# OpenAGBoardPart2.net
KiCad netlist of a schematic drawn in Altium Designer
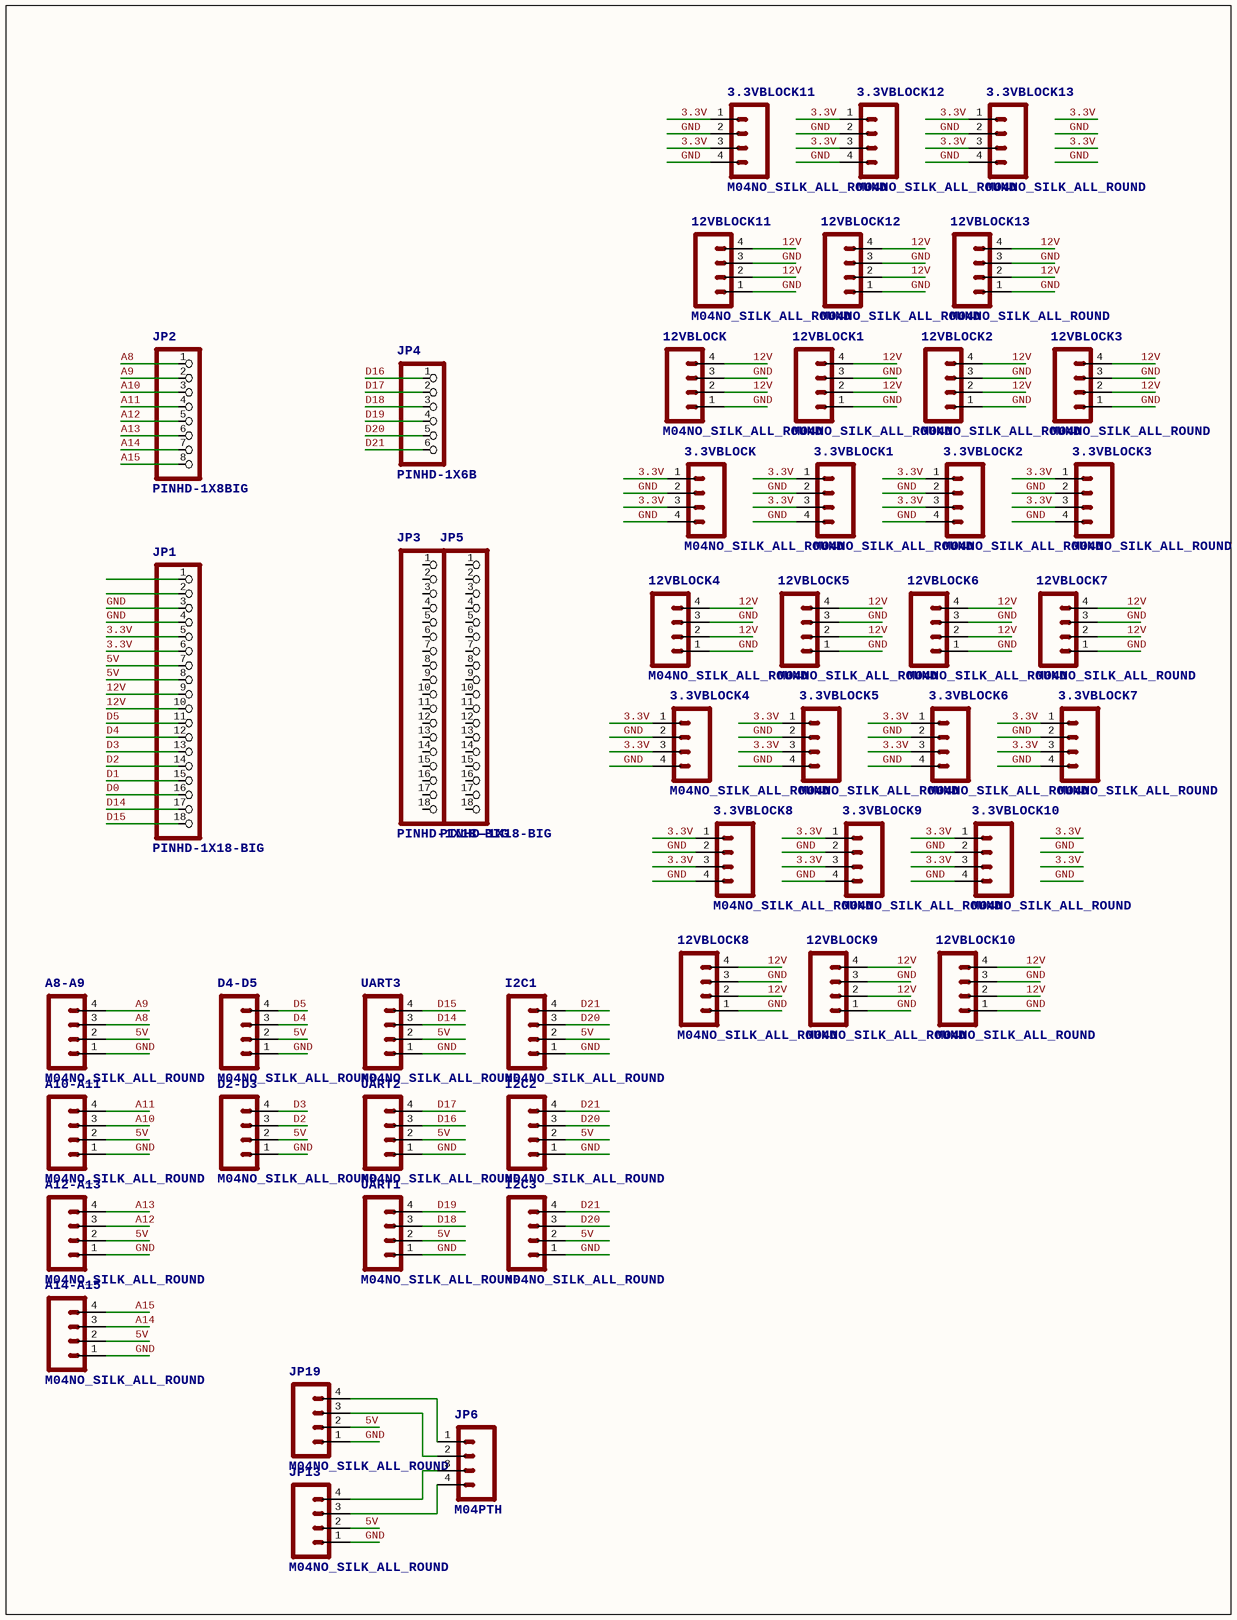
[diagram p0: OpenAGBoardPart2.SchDoc]

(export (version "E")
  (design (tool "Eeschema 10.0.6"))
  (components
    (comp (ref "3.3VBLOCK")
      (value "M04NO_SILK_ALL_ROUND")
      (footprint "1X04_NO_SILK_ALL_ROUND")
      (libsource (lib "SparkFun-Connectors") (part "M04NO_SILK_ALL_ROUND"))
    )
    (comp (ref "3.3VBLOCK1")
      (value "M04NO_SILK_ALL_ROUND")
      (footprint "1X04_NO_SILK_ALL_ROUND")
      (libsource (lib "SparkFun-Connectors") (part "M04NO_SILK_ALL_ROUND"))
    )
    (comp (ref "3.3VBLOCK2")
      (value "M04NO_SILK_ALL_ROUND")
      (footprint "1X04_NO_SILK_ALL_ROUND")
      (libsource (lib "SparkFun-Connectors") (part "M04NO_SILK_ALL_ROUND"))
    )
    (comp (ref "3.3VBLOCK3")
      (value "M04NO_SILK_ALL_ROUND")
      (footprint "1X04_NO_SILK_ALL_ROUND")
      (libsource (lib "SparkFun-Connectors") (part "M04NO_SILK_ALL_ROUND"))
    )
    (comp (ref "3.3VBLOCK4")
      (value "M04NO_SILK_ALL_ROUND")
      (footprint "1X04_NO_SILK_ALL_ROUND")
      (libsource (lib "SparkFun-Connectors") (part "M04NO_SILK_ALL_ROUND"))
    )
    (comp (ref "3.3VBLOCK5")
      (value "M04NO_SILK_ALL_ROUND")
      (footprint "1X04_NO_SILK_ALL_ROUND")
      (libsource (lib "SparkFun-Connectors") (part "M04NO_SILK_ALL_ROUND"))
    )
    (comp (ref "3.3VBLOCK6")
      (value "M04NO_SILK_ALL_ROUND")
      (footprint "1X04_NO_SILK_ALL_ROUND")
      (libsource (lib "SparkFun-Connectors") (part "M04NO_SILK_ALL_ROUND"))
    )
    (comp (ref "3.3VBLOCK7")
      (value "M04NO_SILK_ALL_ROUND")
      (footprint "1X04_NO_SILK_ALL_ROUND")
      (libsource (lib "SparkFun-Connectors") (part "M04NO_SILK_ALL_ROUND"))
    )
    (comp (ref "3.3VBLOCK8")
      (value "M04NO_SILK_ALL_ROUND")
      (footprint "1X04_NO_SILK_ALL_ROUND")
      (libsource (lib "SparkFun-Connectors") (part "M04NO_SILK_ALL_ROUND"))
    )
    (comp (ref "3.3VBLOCK9")
      (value "M04NO_SILK_ALL_ROUND")
      (footprint "1X04_NO_SILK_ALL_ROUND")
      (libsource (lib "SparkFun-Connectors") (part "M04NO_SILK_ALL_ROUND"))
    )
    (comp (ref "3.3VBLOCK10")
      (value "M04NO_SILK_ALL_ROUND")
      (footprint "1X04_NO_SILK_ALL_ROUND")
      (libsource (lib "SparkFun-Connectors") (part "M04NO_SILK_ALL_ROUND"))
    )
    (comp (ref "3.3VBLOCK11")
      (value "M04NO_SILK_ALL_ROUND")
      (footprint "1X04_NO_SILK_ALL_ROUND")
      (libsource (lib "SparkFun-Connectors") (part "M04NO_SILK_ALL_ROUND"))
    )
    (comp (ref "3.3VBLOCK12")
      (value "M04NO_SILK_ALL_ROUND")
      (footprint "1X04_NO_SILK_ALL_ROUND")
      (libsource (lib "SparkFun-Connectors") (part "M04NO_SILK_ALL_ROUND"))
    )
    (comp (ref "3.3VBLOCK13")
      (value "M04NO_SILK_ALL_ROUND")
      (footprint "1X04_NO_SILK_ALL_ROUND")
      (libsource (lib "SparkFun-Connectors") (part "M04NO_SILK_ALL_ROUND"))
    )
    (comp (ref "12VBLOCK")
      (value "M04NO_SILK_ALL_ROUND")
      (footprint "1X04_NO_SILK_ALL_ROUND")
      (libsource (lib "SparkFun-Connectors") (part "M04NO_SILK_ALL_ROUND"))
    )
    (comp (ref "12VBLOCK1")
      (value "M04NO_SILK_ALL_ROUND")
      (footprint "1X04_NO_SILK_ALL_ROUND")
      (libsource (lib "SparkFun-Connectors") (part "M04NO_SILK_ALL_ROUND"))
    )
    (comp (ref "12VBLOCK2")
      (value "M04NO_SILK_ALL_ROUND")
      (footprint "1X04_NO_SILK_ALL_ROUND")
      (libsource (lib "SparkFun-Connectors") (part "M04NO_SILK_ALL_ROUND"))
    )
    (comp (ref "12VBLOCK3")
      (value "M04NO_SILK_ALL_ROUND")
      (footprint "1X04_NO_SILK_ALL_ROUND")
      (libsource (lib "SparkFun-Connectors") (part "M04NO_SILK_ALL_ROUND"))
    )
    (comp (ref "12VBLOCK4")
      (value "M04NO_SILK_ALL_ROUND")
      (footprint "1X04_NO_SILK_ALL_ROUND")
      (libsource (lib "SparkFun-Connectors") (part "M04NO_SILK_ALL_ROUND"))
    )
    (comp (ref "12VBLOCK5")
      (value "M04NO_SILK_ALL_ROUND")
      (footprint "1X04_NO_SILK_ALL_ROUND")
      (libsource (lib "SparkFun-Connectors") (part "M04NO_SILK_ALL_ROUND"))
    )
    (comp (ref "12VBLOCK6")
      (value "M04NO_SILK_ALL_ROUND")
      (footprint "1X04_NO_SILK_ALL_ROUND")
      (libsource (lib "SparkFun-Connectors") (part "M04NO_SILK_ALL_ROUND"))
    )
    (comp (ref "12VBLOCK7")
      (value "M04NO_SILK_ALL_ROUND")
      (footprint "1X04_NO_SILK_ALL_ROUND")
      (libsource (lib "SparkFun-Connectors") (part "M04NO_SILK_ALL_ROUND"))
    )
    (comp (ref "12VBLOCK8")
      (value "M04NO_SILK_ALL_ROUND")
      (footprint "1X04_NO_SILK_ALL_ROUND")
      (libsource (lib "SparkFun-Connectors") (part "M04NO_SILK_ALL_ROUND"))
    )
    (comp (ref "12VBLOCK9")
      (value "M04NO_SILK_ALL_ROUND")
      (footprint "1X04_NO_SILK_ALL_ROUND")
      (libsource (lib "SparkFun-Connectors") (part "M04NO_SILK_ALL_ROUND"))
    )
    (comp (ref "12VBLOCK10")
      (value "M04NO_SILK_ALL_ROUND")
      (footprint "1X04_NO_SILK_ALL_ROUND")
      (libsource (lib "SparkFun-Connectors") (part "M04NO_SILK_ALL_ROUND"))
    )
    (comp (ref "12VBLOCK11")
      (value "M04NO_SILK_ALL_ROUND")
      (footprint "1X04_NO_SILK_ALL_ROUND")
      (libsource (lib "SparkFun-Connectors") (part "M04NO_SILK_ALL_ROUND"))
    )
    (comp (ref "12VBLOCK12")
      (value "M04NO_SILK_ALL_ROUND")
      (footprint "1X04_NO_SILK_ALL_ROUND")
      (libsource (lib "SparkFun-Connectors") (part "M04NO_SILK_ALL_ROUND"))
    )
    (comp (ref "12VBLOCK13")
      (value "M04NO_SILK_ALL_ROUND")
      (footprint "1X04_NO_SILK_ALL_ROUND")
      (libsource (lib "SparkFun-Connectors") (part "M04NO_SILK_ALL_ROUND"))
    )
    (comp (ref "A8-A9")
      (value "M04NO_SILK_ALL_ROUND")
      (footprint "1X04_NO_SILK_ALL_ROUND")
      (libsource (lib "SparkFun-Connectors") (part "M04NO_SILK_ALL_ROUND"))
    )
    (comp (ref "A10-A11")
      (value "M04NO_SILK_ALL_ROUND")
      (footprint "1X04_NO_SILK_ALL_ROUND")
      (libsource (lib "SparkFun-Connectors") (part "M04NO_SILK_ALL_ROUND"))
    )
    (comp (ref "A12-A13")
      (value "M04NO_SILK_ALL_ROUND")
      (footprint "1X04_NO_SILK_ALL_ROUND")
      (libsource (lib "SparkFun-Connectors") (part "M04NO_SILK_ALL_ROUND"))
    )
    (comp (ref "A14-A15")
      (value "M04NO_SILK_ALL_ROUND")
      (footprint "1X04_NO_SILK_ALL_ROUND")
      (libsource (lib "SparkFun-Connectors") (part "M04NO_SILK_ALL_ROUND"))
    )
    (comp (ref "D2-D3")
      (value "M04NO_SILK_ALL_ROUND")
      (footprint "1X04_NO_SILK_ALL_ROUND")
      (libsource (lib "SparkFun-Connectors") (part "M04NO_SILK_ALL_ROUND"))
    )
    (comp (ref "D4-D5")
      (value "M04NO_SILK_ALL_ROUND")
      (footprint "1X04_NO_SILK_ALL_ROUND")
      (libsource (lib "SparkFun-Connectors") (part "M04NO_SILK_ALL_ROUND"))
    )
    (comp (ref "I2C1")
      (value "M04NO_SILK_ALL_ROUND")
      (footprint "1X04_NO_SILK_ALL_ROUND")
      (libsource (lib "SparkFun-Connectors") (part "M04NO_SILK_ALL_ROUND"))
    )
    (comp (ref "I2C2")
      (value "M04NO_SILK_ALL_ROUND")
      (footprint "1X04_NO_SILK_ALL_ROUND")
      (libsource (lib "SparkFun-Connectors") (part "M04NO_SILK_ALL_ROUND"))
    )
    (comp (ref "I2C3")
      (value "M04NO_SILK_ALL_ROUND")
      (footprint "1X04_NO_SILK_ALL_ROUND")
      (libsource (lib "SparkFun-Connectors") (part "M04NO_SILK_ALL_ROUND"))
    )
    (comp (ref "JP1")
      (value "PINHD-1X18-BIG")
      (footprint "1X18-BIG")
      (description "PIN HEADER")
      (libsource (lib "adafruit") (part "PINHD-1X18-BIG"))
    )
    (comp (ref "JP2")
      (value "PINHD-1X8BIG")
      (footprint "1X08-BIG")
      (description "PIN HEADER")
      (libsource (lib "adafruit") (part "PINHD-1X8BIG"))
    )
    (comp (ref "JP3")
      (value "PINHD-1X18-BIG")
      (footprint "1X18-BIG")
      (description "PIN HEADER")
      (libsource (lib "adafruit") (part "PINHD-1X18-BIG"))
    )
    (comp (ref "JP4")
      (value "PINHD-1X6B")
      (footprint "1X06-BIG")
      (description "PIN HEADER")
      (libsource (lib "adafruit") (part "PINHD-1X6B"))
    )
    (comp (ref "JP5")
      (value "PINHD-1X18-BIG")
      (footprint "1X18-BIG")
      (description "PIN HEADER")
      (libsource (lib "adafruit") (part "PINHD-1X18-BIG"))
    )
    (comp (ref "JP6")
      (value "M04PTH")
      (footprint "1X04")
      (libsource (lib "SparkFun-Connectors") (part "M04PTH"))
    )
    (comp (ref "JP13")
      (value "M04NO_SILK_ALL_ROUND")
      (footprint "1X04_NO_SILK_ALL_ROUND")
      (libsource (lib "SparkFun-Connectors") (part "M04NO_SILK_ALL_ROUND"))
    )
    (comp (ref "JP19")
      (value "M04NO_SILK_ALL_ROUND")
      (footprint "1X04_NO_SILK_ALL_ROUND")
      (libsource (lib "SparkFun-Connectors") (part "M04NO_SILK_ALL_ROUND"))
    )
    (comp (ref "UART1")
      (value "M04NO_SILK_ALL_ROUND")
      (footprint "1X04_NO_SILK_ALL_ROUND")
      (libsource (lib "SparkFun-Connectors") (part "M04NO_SILK_ALL_ROUND"))
    )
    (comp (ref "UART2")
      (value "M04NO_SILK_ALL_ROUND")
      (footprint "1X04_NO_SILK_ALL_ROUND")
      (libsource (lib "SparkFun-Connectors") (part "M04NO_SILK_ALL_ROUND"))
    )
    (comp (ref "UART3")
      (value "M04NO_SILK_ALL_ROUND")
      (footprint "1X04_NO_SILK_ALL_ROUND")
      (libsource (lib "SparkFun-Connectors") (part "M04NO_SILK_ALL_ROUND"))
    )
  )
  (nets
    (net (code "1") (name "/3.3V") (class "Default")
      (node (ref "3.3VBLOCK") (pin "1") (pinfunction "1_1") (pintype "passive"))
      (node (ref "3.3VBLOCK") (pin "3") (pinfunction "3_3") (pintype "passive"))
      (node (ref "3.3VBLOCK1") (pin "1") (pinfunction "1_1") (pintype "passive"))
      (node (ref "3.3VBLOCK1") (pin "3") (pinfunction "3_3") (pintype "passive"))
      (node (ref "3.3VBLOCK10") (pin "1") (pinfunction "1_1") (pintype "passive"))
      (node (ref "3.3VBLOCK10") (pin "3") (pinfunction "3_3") (pintype "passive"))
      (node (ref "3.3VBLOCK11") (pin "1") (pinfunction "1_1") (pintype "passive"))
      (node (ref "3.3VBLOCK11") (pin "3") (pinfunction "3_3") (pintype "passive"))
      (node (ref "3.3VBLOCK12") (pin "1") (pinfunction "1_1") (pintype "passive"))
      (node (ref "3.3VBLOCK12") (pin "3") (pinfunction "3_3") (pintype "passive"))
      (node (ref "3.3VBLOCK13") (pin "1") (pinfunction "1_1") (pintype "passive"))
      (node (ref "3.3VBLOCK13") (pin "3") (pinfunction "3_3") (pintype "passive"))
      (node (ref "3.3VBLOCK2") (pin "1") (pinfunction "1_1") (pintype "passive"))
      (node (ref "3.3VBLOCK2") (pin "3") (pinfunction "3_3") (pintype "passive"))
      (node (ref "3.3VBLOCK3") (pin "1") (pinfunction "1_1") (pintype "passive"))
      (node (ref "3.3VBLOCK3") (pin "3") (pinfunction "3_3") (pintype "passive"))
      (node (ref "3.3VBLOCK4") (pin "1") (pinfunction "1_1") (pintype "passive"))
      (node (ref "3.3VBLOCK4") (pin "3") (pinfunction "3_3") (pintype "passive"))
      (node (ref "3.3VBLOCK5") (pin "1") (pinfunction "1_1") (pintype "passive"))
      (node (ref "3.3VBLOCK5") (pin "3") (pinfunction "3_3") (pintype "passive"))
      (node (ref "3.3VBLOCK6") (pin "1") (pinfunction "1_1") (pintype "passive"))
      (node (ref "3.3VBLOCK6") (pin "3") (pinfunction "3_3") (pintype "passive"))
      (node (ref "3.3VBLOCK7") (pin "1") (pinfunction "1_1") (pintype "passive"))
      (node (ref "3.3VBLOCK7") (pin "3") (pinfunction "3_3") (pintype "passive"))
      (node (ref "3.3VBLOCK8") (pin "1") (pinfunction "1_1") (pintype "passive"))
      (node (ref "3.3VBLOCK8") (pin "3") (pinfunction "3_3") (pintype "passive"))
      (node (ref "3.3VBLOCK9") (pin "1") (pinfunction "1_1") (pintype "passive"))
      (node (ref "3.3VBLOCK9") (pin "3") (pinfunction "3_3") (pintype "passive"))
      (node (ref "JP1") (pin "5") (pinfunction "5_5") (pintype "passive"))
      (node (ref "JP1") (pin "6") (pinfunction "6_6") (pintype "passive"))
    )
    (net (code "2") (name "/5V") (class "Default")
      (node (ref "A10-A11") (pin "2") (pinfunction "2_2") (pintype "passive"))
      (node (ref "A12-A13") (pin "2") (pinfunction "2_2") (pintype "passive"))
      (node (ref "A14-A15") (pin "2") (pinfunction "2_2") (pintype "passive"))
      (node (ref "A8-A9") (pin "2") (pinfunction "2_2") (pintype "passive"))
      (node (ref "D2-D3") (pin "2") (pinfunction "2_2") (pintype "passive"))
      (node (ref "D4-D5") (pin "2") (pinfunction "2_2") (pintype "passive"))
      (node (ref "I2C1") (pin "2") (pinfunction "2_2") (pintype "passive"))
      (node (ref "I2C2") (pin "2") (pinfunction "2_2") (pintype "passive"))
      (node (ref "I2C3") (pin "2") (pinfunction "2_2") (pintype "passive"))
      (node (ref "JP1") (pin "7") (pinfunction "7_7") (pintype "passive"))
      (node (ref "JP1") (pin "8") (pinfunction "8_8") (pintype "passive"))
      (node (ref "JP13") (pin "2") (pinfunction "2_2") (pintype "passive"))
      (node (ref "JP19") (pin "2") (pinfunction "2_2") (pintype "passive"))
      (node (ref "UART1") (pin "2") (pinfunction "2_2") (pintype "passive"))
      (node (ref "UART2") (pin "2") (pinfunction "2_2") (pintype "passive"))
      (node (ref "UART3") (pin "2") (pinfunction "2_2") (pintype "passive"))
    )
    (net (code "3") (name "/12V") (class "Default")
      (node (ref "12VBLOCK") (pin "2") (pinfunction "2_2") (pintype "passive"))
      (node (ref "12VBLOCK") (pin "4") (pinfunction "4_4") (pintype "passive"))
      (node (ref "12VBLOCK1") (pin "2") (pinfunction "2_2") (pintype "passive"))
      (node (ref "12VBLOCK1") (pin "4") (pinfunction "4_4") (pintype "passive"))
      (node (ref "12VBLOCK10") (pin "2") (pinfunction "2_2") (pintype "passive"))
      (node (ref "12VBLOCK10") (pin "4") (pinfunction "4_4") (pintype "passive"))
      (node (ref "12VBLOCK11") (pin "2") (pinfunction "2_2") (pintype "passive"))
      (node (ref "12VBLOCK11") (pin "4") (pinfunction "4_4") (pintype "passive"))
      (node (ref "12VBLOCK12") (pin "2") (pinfunction "2_2") (pintype "passive"))
      (node (ref "12VBLOCK12") (pin "4") (pinfunction "4_4") (pintype "passive"))
      (node (ref "12VBLOCK13") (pin "2") (pinfunction "2_2") (pintype "passive"))
      (node (ref "12VBLOCK13") (pin "4") (pinfunction "4_4") (pintype "passive"))
      (node (ref "12VBLOCK2") (pin "2") (pinfunction "2_2") (pintype "passive"))
      (node (ref "12VBLOCK2") (pin "4") (pinfunction "4_4") (pintype "passive"))
      (node (ref "12VBLOCK3") (pin "2") (pinfunction "2_2") (pintype "passive"))
      (node (ref "12VBLOCK3") (pin "4") (pinfunction "4_4") (pintype "passive"))
      (node (ref "12VBLOCK4") (pin "2") (pinfunction "2_2") (pintype "passive"))
      (node (ref "12VBLOCK4") (pin "4") (pinfunction "4_4") (pintype "passive"))
      (node (ref "12VBLOCK5") (pin "2") (pinfunction "2_2") (pintype "passive"))
      (node (ref "12VBLOCK5") (pin "4") (pinfunction "4_4") (pintype "passive"))
      (node (ref "12VBLOCK6") (pin "2") (pinfunction "2_2") (pintype "passive"))
      (node (ref "12VBLOCK6") (pin "4") (pinfunction "4_4") (pintype "passive"))
      (node (ref "12VBLOCK7") (pin "2") (pinfunction "2_2") (pintype "passive"))
      (node (ref "12VBLOCK7") (pin "4") (pinfunction "4_4") (pintype "passive"))
      (node (ref "12VBLOCK8") (pin "2") (pinfunction "2_2") (pintype "passive"))
      (node (ref "12VBLOCK8") (pin "4") (pinfunction "4_4") (pintype "passive"))
      (node (ref "12VBLOCK9") (pin "2") (pinfunction "2_2") (pintype "passive"))
      (node (ref "12VBLOCK9") (pin "4") (pinfunction "4_4") (pintype "passive"))
      (node (ref "JP1") (pin "10") (pinfunction "10_10") (pintype "passive"))
      (node (ref "JP1") (pin "9") (pinfunction "9_9") (pintype "passive"))
    )
    (net (code "4") (name "/A8") (class "Default")
      (node (ref "A8-A9") (pin "3") (pinfunction "3_3") (pintype "passive"))
      (node (ref "JP2") (pin "1") (pinfunction "1_1") (pintype "passive"))
    )
    (net (code "5") (name "/A9") (class "Default")
      (node (ref "A8-A9") (pin "4") (pinfunction "4_4") (pintype "passive"))
      (node (ref "JP2") (pin "2") (pinfunction "2_2") (pintype "passive"))
    )
    (net (code "6") (name "/A10") (class "Default")
      (node (ref "A10-A11") (pin "3") (pinfunction "3_3") (pintype "passive"))
      (node (ref "JP2") (pin "3") (pinfunction "3_3") (pintype "passive"))
    )
    (net (code "7") (name "/A11") (class "Default")
      (node (ref "A10-A11") (pin "4") (pinfunction "4_4") (pintype "passive"))
      (node (ref "JP2") (pin "4") (pinfunction "4_4") (pintype "passive"))
    )
    (net (code "8") (name "/A12") (class "Default")
      (node (ref "A12-A13") (pin "3") (pinfunction "3_3") (pintype "passive"))
      (node (ref "JP2") (pin "5") (pinfunction "5_5") (pintype "passive"))
    )
    (net (code "9") (name "/A13") (class "Default")
      (node (ref "A12-A13") (pin "4") (pinfunction "4_4") (pintype "passive"))
      (node (ref "JP2") (pin "6") (pinfunction "6_6") (pintype "passive"))
    )
    (net (code "10") (name "/A14") (class "Default")
      (node (ref "A14-A15") (pin "3") (pinfunction "3_3") (pintype "passive"))
      (node (ref "JP2") (pin "7") (pinfunction "7_7") (pintype "passive"))
    )
    (net (code "11") (name "/A15") (class "Default")
      (node (ref "A14-A15") (pin "4") (pinfunction "4_4") (pintype "passive"))
      (node (ref "JP2") (pin "8") (pinfunction "8_8") (pintype "passive"))
    )
    (net (code "12") (name "/D0") (class "Default")
      (node (ref "JP1") (pin "16") (pinfunction "16_16") (pintype "passive"))
    )
    (net (code "13") (name "/D1") (class "Default")
      (node (ref "JP1") (pin "15") (pinfunction "15_15") (pintype "passive"))
    )
    (net (code "14") (name "/D2") (class "Default")
      (node (ref "D2-D3") (pin "3") (pinfunction "3_3") (pintype "passive"))
      (node (ref "JP1") (pin "14") (pinfunction "14_14") (pintype "passive"))
    )
    (net (code "15") (name "/D3") (class "Default")
      (node (ref "D2-D3") (pin "4") (pinfunction "4_4") (pintype "passive"))
      (node (ref "JP1") (pin "13") (pinfunction "13_13") (pintype "passive"))
    )
    (net (code "16") (name "/D4") (class "Default")
      (node (ref "D4-D5") (pin "3") (pinfunction "3_3") (pintype "passive"))
      (node (ref "JP1") (pin "12") (pinfunction "12_12") (pintype "passive"))
    )
    (net (code "17") (name "/D5") (class "Default")
      (node (ref "D4-D5") (pin "4") (pinfunction "4_4") (pintype "passive"))
      (node (ref "JP1") (pin "11") (pinfunction "11_11") (pintype "passive"))
    )
    (net (code "18") (name "/D14") (class "Default")
      (node (ref "JP1") (pin "17") (pinfunction "17_17") (pintype "passive"))
      (node (ref "UART3") (pin "3") (pinfunction "3_3") (pintype "passive"))
    )
    (net (code "19") (name "/D15") (class "Default")
      (node (ref "JP1") (pin "18") (pinfunction "18_18") (pintype "passive"))
      (node (ref "UART3") (pin "4") (pinfunction "4_4") (pintype "passive"))
    )
    (net (code "20") (name "/D16") (class "Default")
      (node (ref "JP4") (pin "1") (pinfunction "1_1") (pintype "passive"))
      (node (ref "UART2") (pin "3") (pinfunction "3_3") (pintype "passive"))
    )
    (net (code "21") (name "/D17") (class "Default")
      (node (ref "JP4") (pin "2") (pinfunction "2_2") (pintype "passive"))
      (node (ref "UART2") (pin "4") (pinfunction "4_4") (pintype "passive"))
    )
    (net (code "22") (name "/D18") (class "Default")
      (node (ref "JP4") (pin "3") (pinfunction "3_3") (pintype "passive"))
      (node (ref "UART1") (pin "3") (pinfunction "3_3") (pintype "passive"))
    )
    (net (code "23") (name "/D19") (class "Default")
      (node (ref "JP4") (pin "4") (pinfunction "4_4") (pintype "passive"))
      (node (ref "UART1") (pin "4") (pinfunction "4_4") (pintype "passive"))
    )
    (net (code "24") (name "/D20") (class "Default")
      (node (ref "I2C1") (pin "3") (pinfunction "3_3") (pintype "passive"))
      (node (ref "I2C2") (pin "3") (pinfunction "3_3") (pintype "passive"))
      (node (ref "I2C3") (pin "3") (pinfunction "3_3") (pintype "passive"))
      (node (ref "JP4") (pin "5") (pinfunction "5_5") (pintype "passive"))
    )
    (net (code "25") (name "/D21") (class "Default")
      (node (ref "I2C1") (pin "4") (pinfunction "4_4") (pintype "passive"))
      (node (ref "I2C2") (pin "4") (pinfunction "4_4") (pintype "passive"))
      (node (ref "I2C3") (pin "4") (pinfunction "4_4") (pintype "passive"))
      (node (ref "JP4") (pin "6") (pinfunction "6_6") (pintype "passive"))
    )
    (net (code "26") (name "/GND") (class "Default")
      (node (ref "12VBLOCK") (pin "1") (pinfunction "1_1") (pintype "passive"))
      (node (ref "12VBLOCK") (pin "3") (pinfunction "3_3") (pintype "passive"))
      (node (ref "12VBLOCK1") (pin "1") (pinfunction "1_1") (pintype "passive"))
      (node (ref "12VBLOCK1") (pin "3") (pinfunction "3_3") (pintype "passive"))
      (node (ref "12VBLOCK10") (pin "1") (pinfunction "1_1") (pintype "passive"))
      (node (ref "12VBLOCK10") (pin "3") (pinfunction "3_3") (pintype "passive"))
      (node (ref "12VBLOCK11") (pin "1") (pinfunction "1_1") (pintype "passive"))
      (node (ref "12VBLOCK11") (pin "3") (pinfunction "3_3") (pintype "passive"))
      (node (ref "12VBLOCK12") (pin "1") (pinfunction "1_1") (pintype "passive"))
      (node (ref "12VBLOCK12") (pin "3") (pinfunction "3_3") (pintype "passive"))
      (node (ref "12VBLOCK13") (pin "1") (pinfunction "1_1") (pintype "passive"))
      (node (ref "12VBLOCK13") (pin "3") (pinfunction "3_3") (pintype "passive"))
      (node (ref "12VBLOCK2") (pin "1") (pinfunction "1_1") (pintype "passive"))
      (node (ref "12VBLOCK2") (pin "3") (pinfunction "3_3") (pintype "passive"))
      (node (ref "12VBLOCK3") (pin "1") (pinfunction "1_1") (pintype "passive"))
      (node (ref "12VBLOCK3") (pin "3") (pinfunction "3_3") (pintype "passive"))
      (node (ref "12VBLOCK4") (pin "1") (pinfunction "1_1") (pintype "passive"))
      (node (ref "12VBLOCK4") (pin "3") (pinfunction "3_3") (pintype "passive"))
      (node (ref "12VBLOCK5") (pin "1") (pinfunction "1_1") (pintype "passive"))
      (node (ref "12VBLOCK5") (pin "3") (pinfunction "3_3") (pintype "passive"))
      (node (ref "12VBLOCK6") (pin "1") (pinfunction "1_1") (pintype "passive"))
      (node (ref "12VBLOCK6") (pin "3") (pinfunction "3_3") (pintype "passive"))
      (node (ref "12VBLOCK7") (pin "1") (pinfunction "1_1") (pintype "passive"))
      (node (ref "12VBLOCK7") (pin "3") (pinfunction "3_3") (pintype "passive"))
      (node (ref "12VBLOCK8") (pin "1") (pinfunction "1_1") (pintype "passive"))
      (node (ref "12VBLOCK8") (pin "3") (pinfunction "3_3") (pintype "passive"))
      (node (ref "12VBLOCK9") (pin "1") (pinfunction "1_1") (pintype "passive"))
      (node (ref "12VBLOCK9") (pin "3") (pinfunction "3_3") (pintype "passive"))
      (node (ref "3.3VBLOCK") (pin "2") (pinfunction "2_2") (pintype "passive"))
      (node (ref "3.3VBLOCK") (pin "4") (pinfunction "4_4") (pintype "passive"))
      (node (ref "3.3VBLOCK1") (pin "2") (pinfunction "2_2") (pintype "passive"))
      (node (ref "3.3VBLOCK1") (pin "4") (pinfunction "4_4") (pintype "passive"))
      (node (ref "3.3VBLOCK10") (pin "2") (pinfunction "2_2") (pintype "passive"))
      (node (ref "3.3VBLOCK10") (pin "4") (pinfunction "4_4") (pintype "passive"))
      (node (ref "3.3VBLOCK11") (pin "2") (pinfunction "2_2") (pintype "passive"))
      (node (ref "3.3VBLOCK11") (pin "4") (pinfunction "4_4") (pintype "passive"))
      (node (ref "3.3VBLOCK12") (pin "2") (pinfunction "2_2") (pintype "passive"))
      (node (ref "3.3VBLOCK12") (pin "4") (pinfunction "4_4") (pintype "passive"))
      (node (ref "3.3VBLOCK13") (pin "2") (pinfunction "2_2") (pintype "passive"))
      (node (ref "3.3VBLOCK13") (pin "4") (pinfunction "4_4") (pintype "passive"))
      (node (ref "3.3VBLOCK2") (pin "2") (pinfunction "2_2") (pintype "passive"))
      (node (ref "3.3VBLOCK2") (pin "4") (pinfunction "4_4") (pintype "passive"))
      (node (ref "3.3VBLOCK3") (pin "2") (pinfunction "2_2") (pintype "passive"))
      (node (ref "3.3VBLOCK3") (pin "4") (pinfunction "4_4") (pintype "passive"))
      (node (ref "3.3VBLOCK4") (pin "2") (pinfunction "2_2") (pintype "passive"))
      (node (ref "3.3VBLOCK4") (pin "4") (pinfunction "4_4") (pintype "passive"))
      (node (ref "3.3VBLOCK5") (pin "2") (pinfunction "2_2") (pintype "passive"))
      (node (ref "3.3VBLOCK5") (pin "4") (pinfunction "4_4") (pintype "passive"))
      (node (ref "3.3VBLOCK6") (pin "2") (pinfunction "2_2") (pintype "passive"))
      (node (ref "3.3VBLOCK6") (pin "4") (pinfunction "4_4") (pintype "passive"))
      (node (ref "3.3VBLOCK7") (pin "2") (pinfunction "2_2") (pintype "passive"))
      (node (ref "3.3VBLOCK7") (pin "4") (pinfunction "4_4") (pintype "passive"))
      (node (ref "3.3VBLOCK8") (pin "2") (pinfunction "2_2") (pintype "passive"))
      (node (ref "3.3VBLOCK8") (pin "4") (pinfunction "4_4") (pintype "passive"))
      (node (ref "3.3VBLOCK9") (pin "2") (pinfunction "2_2") (pintype "passive"))
      (node (ref "3.3VBLOCK9") (pin "4") (pinfunction "4_4") (pintype "passive"))
      (node (ref "A10-A11") (pin "1") (pinfunction "1_1") (pintype "passive"))
      (node (ref "A12-A13") (pin "1") (pinfunction "1_1") (pintype "passive"))
      (node (ref "A14-A15") (pin "1") (pinfunction "1_1") (pintype "passive"))
      (node (ref "A8-A9") (pin "1") (pinfunction "1_1") (pintype "passive"))
      (node (ref "D2-D3") (pin "1") (pinfunction "1_1") (pintype "passive"))
      (node (ref "D4-D5") (pin "1") (pinfunction "1_1") (pintype "passive"))
      (node (ref "I2C1") (pin "1") (pinfunction "1_1") (pintype "passive"))
      (node (ref "I2C2") (pin "1") (pinfunction "1_1") (pintype "passive"))
      (node (ref "I2C3") (pin "1") (pinfunction "1_1") (pintype "passive"))
      (node (ref "JP1") (pin "3") (pinfunction "3_3") (pintype "passive"))
      (node (ref "JP1") (pin "4") (pinfunction "4_4") (pintype "passive"))
      (node (ref "JP13") (pin "1") (pinfunction "1_1") (pintype "passive"))
      (node (ref "JP19") (pin "1") (pinfunction "1_1") (pintype "passive"))
      (node (ref "UART1") (pin "1") (pinfunction "1_1") (pintype "passive"))
      (node (ref "UART2") (pin "1") (pinfunction "1_1") (pintype "passive"))
      (node (ref "UART3") (pin "1") (pinfunction "1_1") (pintype "passive"))
    )
    (net (code "27") (name "Net-(JP13-Pad3)") (class "Default")
      (node (ref "JP13") (pin "3") (pinfunction "3_3") (pintype "passive"))
      (node (ref "JP6") (pin "4") (pinfunction "4_4") (pintype "passive"))
    )
    (net (code "28") (name "Net-(JP13-Pad4)") (class "Default")
      (node (ref "JP13") (pin "4") (pinfunction "4_4") (pintype "passive"))
      (node (ref "JP6") (pin "3") (pinfunction "3_3") (pintype "passive"))
    )
    (net (code "29") (name "Net-(JP19-Pad3)") (class "Default")
      (node (ref "JP19") (pin "3") (pinfunction "3_3") (pintype "passive"))
      (node (ref "JP6") (pin "2") (pinfunction "2_2") (pintype "passive"))
    )
    (net (code "30") (name "Net-(JP19-Pad4)") (class "Default")
      (node (ref "JP19") (pin "4") (pinfunction "4_4") (pintype "passive"))
      (node (ref "JP6") (pin "1") (pinfunction "1_1") (pintype "passive"))
    )
    (net (code "31") (name "unconnected-(JP1-Pad1)") (class "Default")
      (node (ref "JP1") (pin "1") (pinfunction "1_1") (pintype "passive"))
    )
    (net (code "32") (name "unconnected-(JP1-Pad2)") (class "Default")
      (node (ref "JP1") (pin "2") (pinfunction "2_2") (pintype "passive"))
    )
    (net (code "33") (name "unconnected-(JP3-Pad1)") (class "Default")
      (node (ref "JP3") (pin "1") (pinfunction "1_1") (pintype "passive"))
    )
    (net (code "34") (name "unconnected-(JP3-Pad2)") (class "Default")
      (node (ref "JP3") (pin "2") (pinfunction "2_2") (pintype "passive"))
    )
    (net (code "35") (name "unconnected-(JP3-Pad3)") (class "Default")
      (node (ref "JP3") (pin "3") (pinfunction "3_3") (pintype "passive"))
    )
    (net (code "36") (name "unconnected-(JP3-Pad4)") (class "Default")
      (node (ref "JP3") (pin "4") (pinfunction "4_4") (pintype "passive"))
    )
    (net (code "37") (name "unconnected-(JP3-Pad5)") (class "Default")
      (node (ref "JP3") (pin "5") (pinfunction "5_5") (pintype "passive"))
    )
    (net (code "38") (name "unconnected-(JP3-Pad6)") (class "Default")
      (node (ref "JP3") (pin "6") (pinfunction "6_6") (pintype "passive"))
    )
    (net (code "39") (name "unconnected-(JP3-Pad7)") (class "Default")
      (node (ref "JP3") (pin "7") (pinfunction "7_7") (pintype "passive"))
    )
    (net (code "40") (name "unconnected-(JP3-Pad8)") (class "Default")
      (node (ref "JP3") (pin "8") (pinfunction "8_8") (pintype "passive"))
    )
    (net (code "41") (name "unconnected-(JP3-Pad9)") (class "Default")
      (node (ref "JP3") (pin "9") (pinfunction "9_9") (pintype "passive"))
    )
    (net (code "42") (name "unconnected-(JP3-Pad10)") (class "Default")
      (node (ref "JP3") (pin "10") (pinfunction "10_10") (pintype "passive"))
    )
    (net (code "43") (name "unconnected-(JP3-Pad11)") (class "Default")
      (node (ref "JP3") (pin "11") (pinfunction "11_11") (pintype "passive"))
    )
    (net (code "44") (name "unconnected-(JP3-Pad12)") (class "Default")
      (node (ref "JP3") (pin "12") (pinfunction "12_12") (pintype "passive"))
    )
    (net (code "45") (name "unconnected-(JP3-Pad13)") (class "Default")
      (node (ref "JP3") (pin "13") (pinfunction "13_13") (pintype "passive"))
    )
    (net (code "46") (name "unconnected-(JP3-Pad14)") (class "Default")
      (node (ref "JP3") (pin "14") (pinfunction "14_14") (pintype "passive"))
    )
    (net (code "47") (name "unconnected-(JP3-Pad15)") (class "Default")
      (node (ref "JP3") (pin "15") (pinfunction "15_15") (pintype "passive"))
    )
    (net (code "48") (name "unconnected-(JP3-Pad16)") (class "Default")
      (node (ref "JP3") (pin "16") (pinfunction "16_16") (pintype "passive"))
    )
    (net (code "49") (name "unconnected-(JP3-Pad17)") (class "Default")
      (node (ref "JP3") (pin "17") (pinfunction "17_17") (pintype "passive"))
    )
    (net (code "50") (name "unconnected-(JP3-Pad18)") (class "Default")
      (node (ref "JP3") (pin "18") (pinfunction "18_18") (pintype "passive"))
    )
    (net (code "51") (name "unconnected-(JP5-Pad1)") (class "Default")
      (node (ref "JP5") (pin "1") (pinfunction "1_1") (pintype "passive"))
    )
    (net (code "52") (name "unconnected-(JP5-Pad2)") (class "Default")
      (node (ref "JP5") (pin "2") (pinfunction "2_2") (pintype "passive"))
    )
    (net (code "53") (name "unconnected-(JP5-Pad3)") (class "Default")
      (node (ref "JP5") (pin "3") (pinfunction "3_3") (pintype "passive"))
    )
    (net (code "54") (name "unconnected-(JP5-Pad4)") (class "Default")
      (node (ref "JP5") (pin "4") (pinfunction "4_4") (pintype "passive"))
    )
    (net (code "55") (name "unconnected-(JP5-Pad5)") (class "Default")
      (node (ref "JP5") (pin "5") (pinfunction "5_5") (pintype "passive"))
    )
    (net (code "56") (name "unconnected-(JP5-Pad6)") (class "Default")
      (node (ref "JP5") (pin "6") (pinfunction "6_6") (pintype "passive"))
    )
    (net (code "57") (name "unconnected-(JP5-Pad7)") (class "Default")
      (node (ref "JP5") (pin "7") (pinfunction "7_7") (pintype "passive"))
    )
    (net (code "58") (name "unconnected-(JP5-Pad8)") (class "Default")
      (node (ref "JP5") (pin "8") (pinfunction "8_8") (pintype "passive"))
    )
    (net (code "59") (name "unconnected-(JP5-Pad9)") (class "Default")
      (node (ref "JP5") (pin "9") (pinfunction "9_9") (pintype "passive"))
    )
    (net (code "60") (name "unconnected-(JP5-Pad10)") (class "Default")
      (node (ref "JP5") (pin "10") (pinfunction "10_10") (pintype "passive"))
    )
    (net (code "61") (name "unconnected-(JP5-Pad11)") (class "Default")
      (node (ref "JP5") (pin "11") (pinfunction "11_11") (pintype "passive"))
    )
    (net (code "62") (name "unconnected-(JP5-Pad12)") (class "Default")
      (node (ref "JP5") (pin "12") (pinfunction "12_12") (pintype "passive"))
    )
    (net (code "63") (name "unconnected-(JP5-Pad13)") (class "Default")
      (node (ref "JP5") (pin "13") (pinfunction "13_13") (pintype "passive"))
    )
    (net (code "64") (name "unconnected-(JP5-Pad14)") (class "Default")
      (node (ref "JP5") (pin "14") (pinfunction "14_14") (pintype "passive"))
    )
    (net (code "65") (name "unconnected-(JP5-Pad15)") (class "Default")
      (node (ref "JP5") (pin "15") (pinfunction "15_15") (pintype "passive"))
    )
    (net (code "66") (name "unconnected-(JP5-Pad16)") (class "Default")
      (node (ref "JP5") (pin "16") (pinfunction "16_16") (pintype "passive"))
    )
    (net (code "67") (name "unconnected-(JP5-Pad17)") (class "Default")
      (node (ref "JP5") (pin "17") (pinfunction "17_17") (pintype "passive"))
    )
    (net (code "68") (name "unconnected-(JP5-Pad18)") (class "Default")
      (node (ref "JP5") (pin "18") (pinfunction "18_18") (pintype "passive"))
    )
  )
)
